# BrewMonitor-v1_0.net
KiCad netlist of a schematic drawn in EAGLE
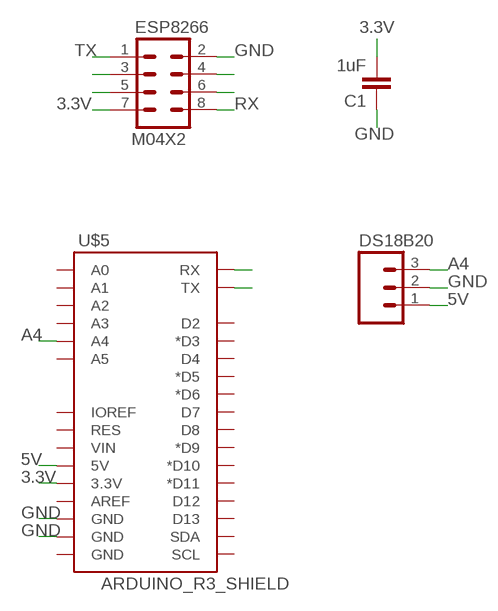
[diagram p0: schematic, sheet 1]

(export (version "E")
  (design (tool "Eeschema 10.0.6"))
  (components
    (comp (ref "C1")
      (value "1uF")
      (footprint "eagle-import:CAP-PTH-SMALL")
      (libsource (lib "eagle-import") (part "CAPPTH"))
    )
    (comp (ref "DS18B20")
      (value "M03SCREW")
      (footprint "eagle-import:SCREWTERMINAL-3.5MM-3")
      (libsource (lib "eagle-import") (part "M03SCREW"))
    )
    (comp (ref "ESP8266")
      (value "M04X2")
      (footprint "eagle-import:2X4")
      (libsource (lib "eagle-import") (part "M04X2"))
    )
    (comp (ref "U$5")
      (value "ARDUINO_R3_SHIELD")
      (footprint "eagle-import:UNO_R3_SHIELD")
      (libsource (lib "eagle-import") (part "ARDUINO_R3_SHIELD"))
    )
  )
  (nets
    (net (code "1") (name "/3.3V") (class "Default")
      (node (ref "C1") (pin "2") (pinfunction "2_2") (pintype "passive"))
      (node (ref "ESP8266") (pin "7") (pinfunction "7_7") (pintype "passive"))
      (node (ref "U$5") (pin "3.3V") (pinfunction "3.3V_3.3V") (pintype "bidirectional"))
    )
    (net (code "2") (name "/5V") (class "Default")
      (node (ref "DS18B20") (pin "1") (pinfunction "1_1") (pintype "passive"))
      (node (ref "U$5") (pin "5V") (pinfunction "5V_5V") (pintype "bidirectional"))
    )
    (net (code "3") (name "/A4") (class "Default")
      (node (ref "DS18B20") (pin "3") (pinfunction "3_3") (pintype "passive"))
      (node (ref "U$5") (pin "A4") (pinfunction "A4_A4") (pintype "bidirectional"))
    )
    (net (code "4") (name "/GND") (class "Default")
      (node (ref "C1") (pin "1") (pinfunction "1_1") (pintype "passive"))
      (node (ref "DS18B20") (pin "2") (pinfunction "2_2") (pintype "passive"))
      (node (ref "ESP8266") (pin "2") (pinfunction "2_2") (pintype "passive"))
      (node (ref "U$5") (pin "GND@1") (pinfunction "GND_GND@1") (pintype "bidirectional"))
      (node (ref "U$5") (pin "GND@2") (pinfunction "GND_GND@2") (pintype "bidirectional"))
    )
    (net (code "5") (name "/RX") (class "Default")
      (node (ref "ESP8266") (pin "8") (pinfunction "8_8") (pintype "passive"))
      (node (ref "U$5") (pin "RX") (pinfunction "RX_RX") (pintype "bidirectional"))
    )
    (net (code "6") (name "/TX") (class "Default")
      (node (ref "ESP8266") (pin "1") (pinfunction "1_1") (pintype "passive"))
      (node (ref "U$5") (pin "TX") (pinfunction "TX_TX") (pintype "bidirectional"))
    )
    (net (code "7") (name "unconnected-(ESP8266-Pad3)") (class "Default")
      (node (ref "ESP8266") (pin "3") (pinfunction "3_3") (pintype "passive"))
    )
    (net (code "8") (name "unconnected-(ESP8266-Pad4)") (class "Default")
      (node (ref "ESP8266") (pin "4") (pinfunction "4_4") (pintype "passive"))
    )
    (net (code "9") (name "unconnected-(ESP8266-Pad5)") (class "Default")
      (node (ref "ESP8266") (pin "5") (pinfunction "5_5") (pintype "passive"))
    )
    (net (code "10") (name "unconnected-(ESP8266-Pad6)") (class "Default")
      (node (ref "ESP8266") (pin "6") (pinfunction "6_6") (pintype "passive"))
    )
    (net (code "11") (name "unconnected-(U$5-*D3-PadD3)") (class "Default")
      (node (ref "U$5") (pin "D3") (pinfunction "*D3_D3") (pintype "bidirectional"))
    )
    (net (code "12") (name "unconnected-(U$5-*D5-PadD5)") (class "Default")
      (node (ref "U$5") (pin "D5") (pinfunction "*D5_D5") (pintype "bidirectional"))
    )
    (net (code "13") (name "unconnected-(U$5-*D6-PadD6)") (class "Default")
      (node (ref "U$5") (pin "D6") (pinfunction "*D6_D6") (pintype "bidirectional"))
    )
    (net (code "14") (name "unconnected-(U$5-*D9-PadD9)") (class "Default")
      (node (ref "U$5") (pin "D9") (pinfunction "*D9_D9") (pintype "bidirectional"))
    )
    (net (code "15") (name "unconnected-(U$5-*D10-PadD10)") (class "Default")
      (node (ref "U$5") (pin "D10") (pinfunction "*D10_D10") (pintype "bidirectional"))
    )
    (net (code "16") (name "unconnected-(U$5-*D11-PadD11)") (class "Default")
      (node (ref "U$5") (pin "D11") (pinfunction "*D11_D11") (pintype "bidirectional"))
    )
    (net (code "17") (name "unconnected-(U$5-GND-PadGND@0)") (class "Default")
      (node (ref "U$5") (pin "GND@0") (pinfunction "GND_GND@0") (pintype "bidirectional"))
    )
    (net (code "18") (name "unconnected-(U$5-PadA0)") (class "Default")
      (node (ref "U$5") (pin "A0") (pinfunction "A0_A0") (pintype "bidirectional"))
    )
    (net (code "19") (name "unconnected-(U$5-PadA1)") (class "Default")
      (node (ref "U$5") (pin "A1") (pinfunction "A1_A1") (pintype "bidirectional"))
    )
    (net (code "20") (name "unconnected-(U$5-PadA2)") (class "Default")
      (node (ref "U$5") (pin "A2") (pinfunction "A2_A2") (pintype "bidirectional"))
    )
    (net (code "21") (name "unconnected-(U$5-PadA3)") (class "Default")
      (node (ref "U$5") (pin "A3") (pinfunction "A3_A3") (pintype "bidirectional"))
    )
    (net (code "22") (name "unconnected-(U$5-PadA5)") (class "Default")
      (node (ref "U$5") (pin "A5") (pinfunction "A5_A5") (pintype "bidirectional"))
    )
    (net (code "23") (name "unconnected-(U$5-PadAREF)") (class "Default")
      (node (ref "U$5") (pin "AREF") (pinfunction "AREF_AREF") (pintype "bidirectional"))
    )
    (net (code "24") (name "unconnected-(U$5-PadD2)") (class "Default")
      (node (ref "U$5") (pin "D2") (pinfunction "D2_D2") (pintype "bidirectional"))
    )
    (net (code "25") (name "unconnected-(U$5-PadD4)") (class "Default")
      (node (ref "U$5") (pin "D4") (pinfunction "D4_D4") (pintype "bidirectional"))
    )
    (net (code "26") (name "unconnected-(U$5-PadD7)") (class "Default")
      (node (ref "U$5") (pin "D7") (pinfunction "D7_D7") (pintype "bidirectional"))
    )
    (net (code "27") (name "unconnected-(U$5-PadD8)") (class "Default")
      (node (ref "U$5") (pin "D8") (pinfunction "D8_D8") (pintype "bidirectional"))
    )
    (net (code "28") (name "unconnected-(U$5-PadD12)") (class "Default")
      (node (ref "U$5") (pin "D12") (pinfunction "D12_D12") (pintype "bidirectional"))
    )
    (net (code "29") (name "unconnected-(U$5-PadD13)") (class "Default")
      (node (ref "U$5") (pin "D13") (pinfunction "D13_D13") (pintype "bidirectional"))
    )
    (net (code "30") (name "unconnected-(U$5-PadIOREF)") (class "Default")
      (node (ref "U$5") (pin "IOREF") (pinfunction "IOREF_IOREF") (pintype "bidirectional"))
    )
    (net (code "31") (name "unconnected-(U$5-PadRES)") (class "Default")
      (node (ref "U$5") (pin "RES") (pinfunction "RES_RES") (pintype "bidirectional"))
    )
    (net (code "32") (name "unconnected-(U$5-PadSCL)") (class "Default")
      (node (ref "U$5") (pin "SCL") (pinfunction "SCL_SCL") (pintype "bidirectional"))
    )
    (net (code "33") (name "unconnected-(U$5-PadSDA)") (class "Default")
      (node (ref "U$5") (pin "SDA") (pinfunction "SDA_SDA") (pintype "bidirectional"))
    )
    (net (code "34") (name "unconnected-(U$5-PadVIN)") (class "Default")
      (node (ref "U$5") (pin "VIN") (pinfunction "VIN_VIN") (pintype "bidirectional"))
    )
  )
)
